# Schematic.net
KiCad netlist of a schematic drawn in EAGLE
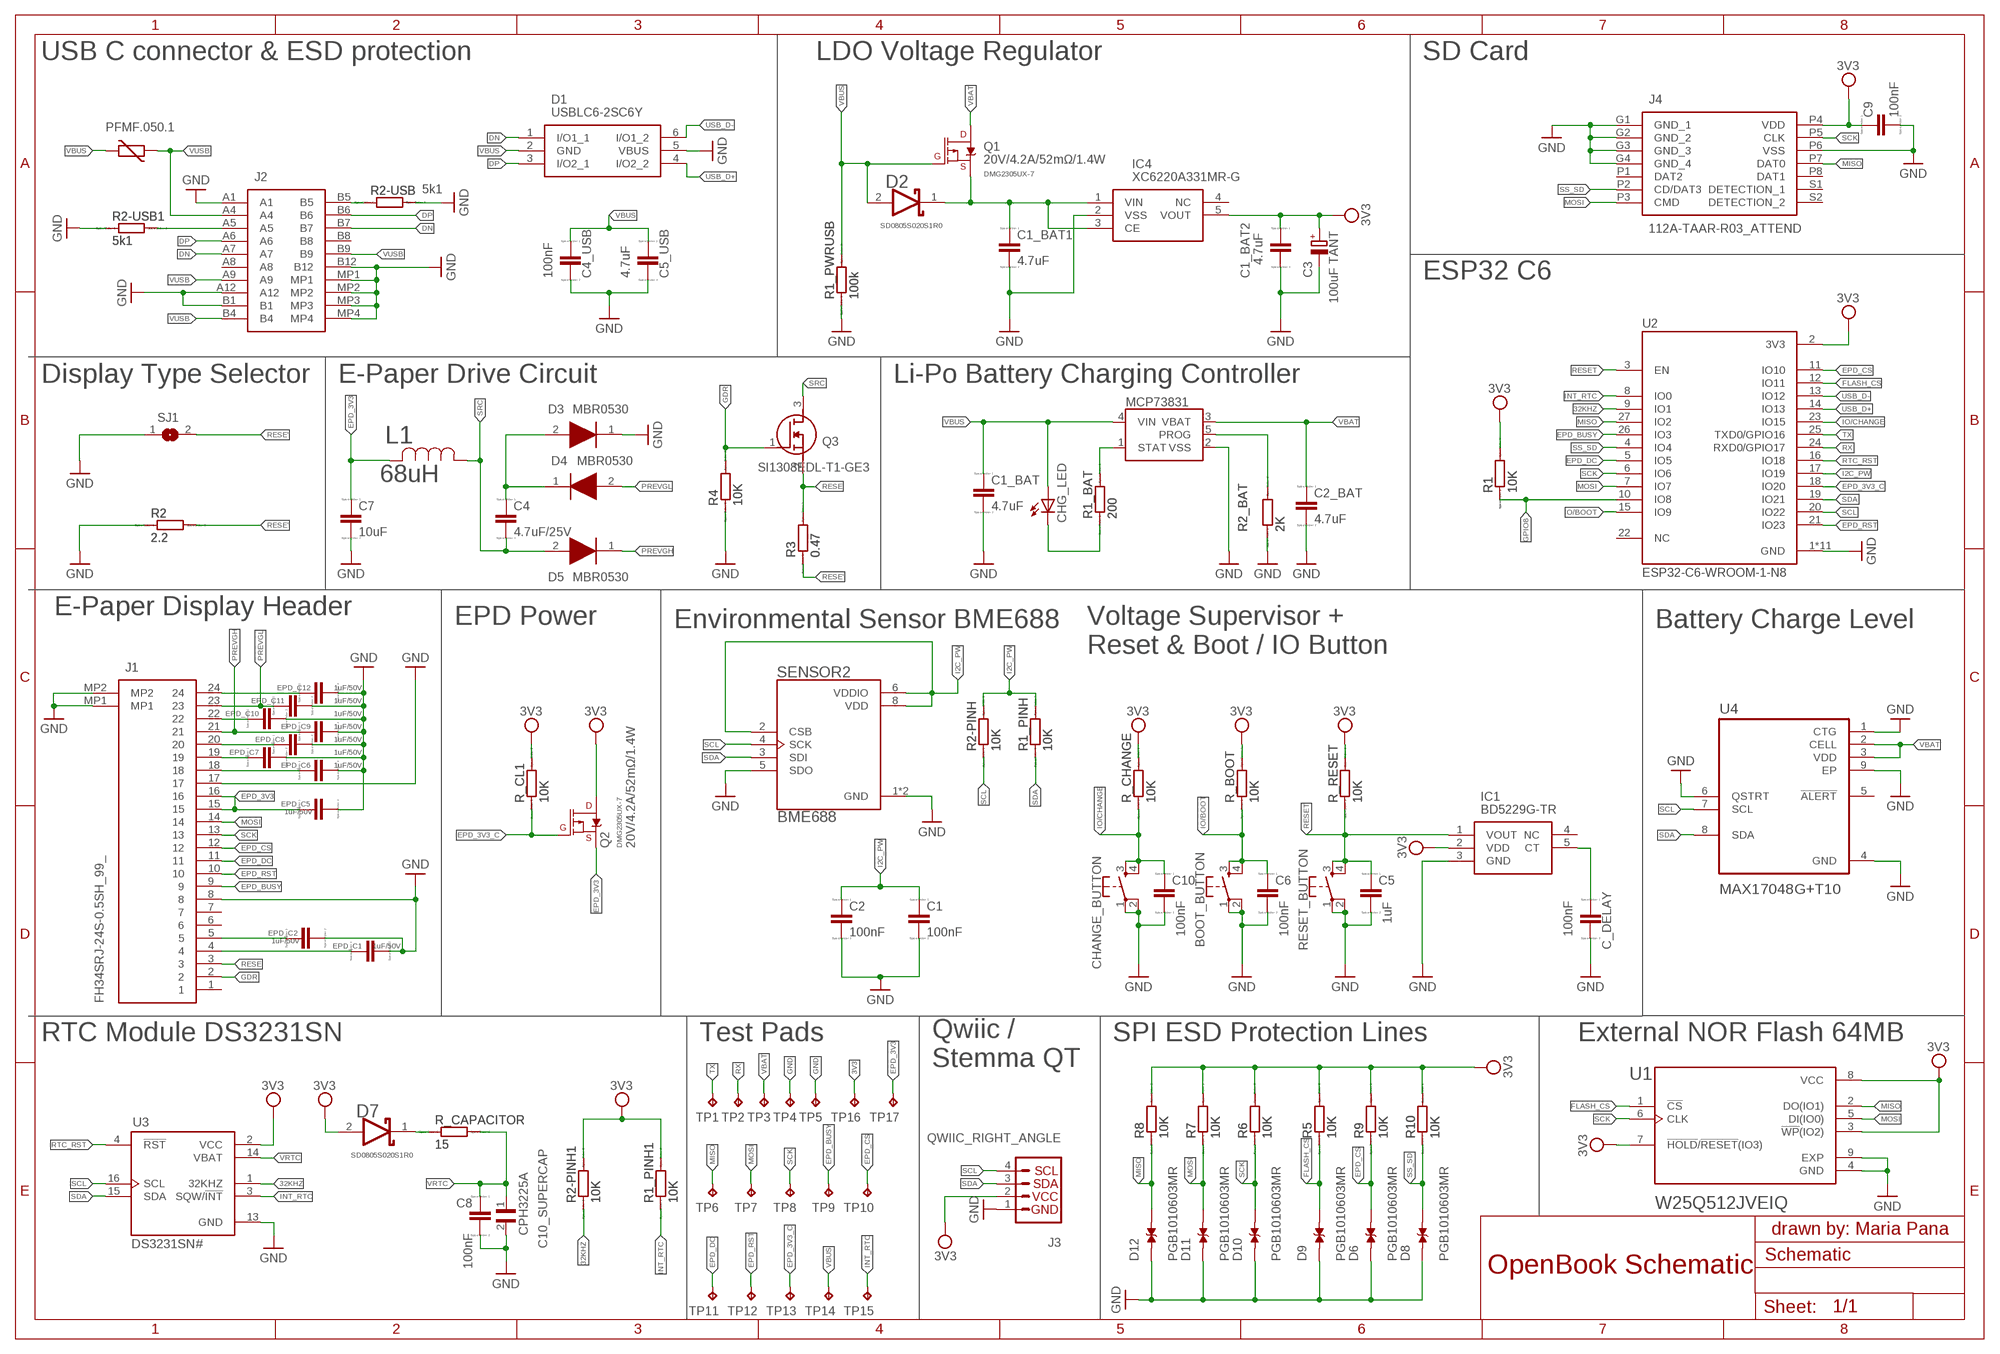
[diagram p0: schematic, sheet 1]

(export (version "E")
  (design (tool "Eeschema 10.0.6"))
  (components
    (comp (ref "BOOT_BUTTON")
      (value "BUTTON_CUSYOMV1")
      (footprint "eagle-import:MYBUTTON")
      (libsource (lib "eagle-import") (part "BUTTON_CUSYOMV1"))
    )
    (comp (ref "C1")
      (value "100nF")
      (footprint "eagle-import:ESP32_WROVER_EAGLE-LTSPICE_C0402")
      (libsource (lib "eagle-import") (part "ESP32_WROVER_EAGLE-LTSPICE_CC0402"))
    )
    (comp (ref "C1_BAT")
      (value "4.7uF")
      (footprint "eagle-import:EAGLE-LTSPICE_C0402")
      (libsource (lib "eagle-import") (part "EAGLE-LTSPICE_CC0402"))
    )
    (comp (ref "C1_BAT1")
      (value "4.7uF")
      (footprint "eagle-import:EAGLE-LTSPICE_C0402")
      (libsource (lib "eagle-import") (part "EAGLE-LTSPICE_CC0402"))
    )
    (comp (ref "C1_BAT2")
      (value "4.7uF")
      (footprint "eagle-import:EAGLE-LTSPICE_C0402")
      (libsource (lib "eagle-import") (part "EAGLE-LTSPICE_CC0402"))
    )
    (comp (ref "C2")
      (value "100nF")
      (footprint "eagle-import:ESP32_WROVER_EAGLE-LTSPICE_C0402")
      (libsource (lib "eagle-import") (part "ESP32_WROVER_EAGLE-LTSPICE_CC0402"))
    )
    (comp (ref "C2_BAT")
      (value "4.7uF")
      (footprint "eagle-import:EAGLE-LTSPICE_C0402")
      (libsource (lib "eagle-import") (part "EAGLE-LTSPICE_CC0402"))
    )
    (comp (ref "C3")
      (value "100uF TANT")
      (footprint "eagle-import:RCL_CT3528")
      (libsource (lib "eagle-import") (part "RCL_CPOL-EUCT3528"))
    )
    (comp (ref "C4")
      (value "4.7uF/25V")
      (footprint "eagle-import:EAGLE-LTSPICE_C0402")
      (libsource (lib "eagle-import") (part "EAGLE-LTSPICE_CC0402"))
    )
    (comp (ref "C4_USB")
      (value "100nF")
      (footprint "eagle-import:EAGLE-LTSPICE_C0402")
      (libsource (lib "eagle-import") (part "EAGLE-LTSPICE_CC0402"))
    )
    (comp (ref "C5")
      (value "1uF")
      (footprint "eagle-import:ESP32_WROVER_EAGLE-LTSPICE_C0402")
      (libsource (lib "eagle-import") (part "ESP32_WROVER_EAGLE-LTSPICE_CC0402"))
    )
    (comp (ref "C5_USB")
      (value "4.7uF")
      (footprint "eagle-import:EAGLE-LTSPICE_C0402")
      (libsource (lib "eagle-import") (part "EAGLE-LTSPICE_CC0402"))
    )
    (comp (ref "C6")
      (value "100nF")
      (footprint "eagle-import:ESP32_WROVER_EAGLE-LTSPICE_C0402")
      (libsource (lib "eagle-import") (part "ESP32_WROVER_EAGLE-LTSPICE_CC0402"))
    )
    (comp (ref "C7")
      (value "10uF")
      (footprint "eagle-import:EAGLE-LTSPICE_C0402")
      (libsource (lib "eagle-import") (part "EAGLE-LTSPICE_CC0402"))
    )
    (comp (ref "C8")
      (value "100nF")
      (footprint "eagle-import:ESP32_WROVER_EAGLE-LTSPICE_C0402")
      (libsource (lib "eagle-import") (part "ESP32_WROVER_EAGLE-LTSPICE_CC0402"))
    )
    (comp (ref "C9")
      (value "100nF")
      (footprint "eagle-import:EAGLE-LTSPICE_C0402")
      (libsource (lib "eagle-import") (part "EAGLE-LTSPICE_CC0402"))
    )
    (comp (ref "C10")
      (value "100nF")
      (footprint "eagle-import:ESP32_WROVER_EAGLE-LTSPICE_C0402")
      (libsource (lib "eagle-import") (part "ESP32_WROVER_EAGLE-LTSPICE_CC0402"))
    )
    (comp (ref "C10_SUPERCAP")
      (value "CPH3225A")
      (footprint "eagle-import:CAPCP3225X100N")
      (fields (field (name "MF") "Seiko Instruments"))
      (libsource (lib "eagle-import") (part "CPH3225A"))
    )
    (comp (ref "CHANGE_BUTTON")
      (value "BUTTON_CUSYOMV1")
      (footprint "eagle-import:MYBUTTON")
      (libsource (lib "eagle-import") (part "BUTTON_CUSYOMV1"))
    )
    (comp (ref "CHG_LED")
      (value "ADAFRUIT_LEDCHIP-LED0603")
      (footprint "eagle-import:ADAFRUIT_CHIP-LED0603")
      (libsource (lib "eagle-import") (part "ADAFRUIT_LEDCHIP-LED0603"))
    )
    (comp (ref "C_DELAY")
      (value "100nF")
      (footprint "eagle-import:ESP32_WROVER_EAGLE-LTSPICE_C0402")
      (libsource (lib "eagle-import") (part "ESP32_WROVER_EAGLE-LTSPICE_CC0402"))
    )
    (comp (ref "D1")
      (value "USBLC6-2SC6Y")
      (footprint "eagle-import:SOT95P280X145-6N")
      (fields (field (name "MF") "STMicroelectronics"))
      (libsource (lib "eagle-import") (part "USBLC6-2SC6Y"))
    )
    (comp (ref "D2")
      (value "SD0805S020S1R0")
      (footprint "eagle-import:ESP32_WROVER_AVX---SD0805S020S1R0_AVX_SD0805S020S1R0_0")
      (fields
        (field (name "DIGIKEY_PART_NUMBER") "478-7800-1-ND")
        (field (name "MF") "AVX")
        (field (name "MOUSER_PART_NUMBER") "581-SD0805S020S1R0")
      )
      (libsource (lib "eagle-import") (part "ESP32_WROVER_AVX---SD0805S020S1R0_AVX_SD0805S020S1R0_0_0AVX_SD0805S020S1R0_0_0"))
    )
    (comp (ref "D3")
      (value "MBR0530")
      (footprint "eagle-import:SOD3716X135N")
      (fields (field (name "MF") "ON Semiconductor"))
      (libsource (lib "eagle-import") (part "MBR0530"))
    )
    (comp (ref "D4")
      (value "MBR0530")
      (footprint "eagle-import:SOD3716X135N")
      (fields (field (name "MF") "ON Semiconductor"))
      (libsource (lib "eagle-import") (part "MBR0530"))
    )
    (comp (ref "D5")
      (value "MBR0530")
      (footprint "eagle-import:SOD3716X135N")
      (fields (field (name "MF") "ON Semiconductor"))
      (libsource (lib "eagle-import") (part "MBR0530"))
    )
    (comp (ref "D6")
      (value "PGB1010603MR")
      (footprint "eagle-import:DIOC1608X36N")
      (fields (field (name "MF") "Littelfuse Inc."))
      (libsource (lib "eagle-import") (part "PGB1010603MR"))
    )
    (comp (ref "D7")
      (value "ESP32_WROVER_AVX---SD0805S020S1R0_AVX_SD0805S020S1R0_0_0AVX_SD0805S020S1R0_0_0")
      (footprint "eagle-import:ESP32_WROVER_AVX---SD0805S020S1R0_AVX_SD0805S020S1R0_0")
      (fields
        (field (name "DIGIKEY_PART_NUMBER") "478-7800-1-ND")
        (field (name "MF") "AVX")
        (field (name "MOUSER_PART_NUMBER") "581-SD0805S020S1R0")
      )
      (libsource (lib "eagle-import") (part "ESP32_WROVER_AVX---SD0805S020S1R0_AVX_SD0805S020S1R0_0_0AVX_SD0805S020S1R0_0_0"))
    )
    (comp (ref "D8")
      (value "PGB1010603MR")
      (footprint "eagle-import:DIOC1608X36N")
      (fields (field (name "MF") "Littelfuse Inc."))
      (libsource (lib "eagle-import") (part "PGB1010603MR"))
    )
    (comp (ref "D9")
      (value "PGB1010603MR")
      (footprint "eagle-import:DIOC1608X36N")
      (fields (field (name "MF") "Littelfuse Inc."))
      (libsource (lib "eagle-import") (part "PGB1010603MR"))
    )
    (comp (ref "D10")
      (value "PGB1010603MR")
      (footprint "eagle-import:DIOC1608X36N")
      (fields (field (name "MF") "Littelfuse Inc."))
      (libsource (lib "eagle-import") (part "PGB1010603MR"))
    )
    (comp (ref "D11")
      (value "PGB1010603MR")
      (footprint "eagle-import:DIOC1608X36N")
      (fields (field (name "MF") "Littelfuse Inc."))
      (libsource (lib "eagle-import") (part "PGB1010603MR"))
    )
    (comp (ref "D12")
      (value "PGB1010603MR")
      (footprint "eagle-import:DIOC1608X36N")
      (fields (field (name "MF") "Littelfuse Inc."))
      (libsource (lib "eagle-import") (part "PGB1010603MR"))
    )
    (comp (ref "EPD_C1")
      (value "1uF/50V")
      (footprint "eagle-import:ESP32_WROVER_EAGLE-LTSPICE_C0402")
      (libsource (lib "eagle-import") (part "ESP32_WROVER_EAGLE-LTSPICE_CC0402"))
    )
    (comp (ref "EPD_C2")
      (value "1uF/50V")
      (footprint "eagle-import:ESP32_WROVER_EAGLE-LTSPICE_C0402")
      (libsource (lib "eagle-import") (part "ESP32_WROVER_EAGLE-LTSPICE_CC0402"))
    )
    (comp (ref "EPD_C5")
      (value "1uF/50V")
      (footprint "eagle-import:ESP32_WROVER_EAGLE-LTSPICE_C0402")
      (libsource (lib "eagle-import") (part "ESP32_WROVER_EAGLE-LTSPICE_CC0402"))
    )
    (comp (ref "EPD_C6")
      (value "1uF/50V")
      (footprint "eagle-import:ESP32_WROVER_EAGLE-LTSPICE_C0402")
      (libsource (lib "eagle-import") (part "ESP32_WROVER_EAGLE-LTSPICE_CC0402"))
    )
    (comp (ref "EPD_C7")
      (value "1uF/50V")
      (footprint "eagle-import:ESP32_WROVER_EAGLE-LTSPICE_C0402")
      (libsource (lib "eagle-import") (part "ESP32_WROVER_EAGLE-LTSPICE_CC0402"))
    )
    (comp (ref "EPD_C8")
      (value "1uF/50V")
      (footprint "eagle-import:ESP32_WROVER_EAGLE-LTSPICE_C0402")
      (libsource (lib "eagle-import") (part "ESP32_WROVER_EAGLE-LTSPICE_CC0402"))
    )
    (comp (ref "EPD_C9")
      (value "1uF/50V")
      (footprint "eagle-import:ESP32_WROVER_EAGLE-LTSPICE_C0402")
      (libsource (lib "eagle-import") (part "ESP32_WROVER_EAGLE-LTSPICE_CC0402"))
    )
    (comp (ref "EPD_C10")
      (value "1uF/50V")
      (footprint "eagle-import:ESP32_WROVER_EAGLE-LTSPICE_C0402")
      (libsource (lib "eagle-import") (part "ESP32_WROVER_EAGLE-LTSPICE_CC0402"))
    )
    (comp (ref "EPD_C11")
      (value "1uF/50V")
      (footprint "eagle-import:ESP32_WROVER_EAGLE-LTSPICE_C0402")
      (libsource (lib "eagle-import") (part "ESP32_WROVER_EAGLE-LTSPICE_CC0402"))
    )
    (comp (ref "EPD_C12")
      (value "1uF/50V")
      (footprint "eagle-import:ESP32_WROVER_EAGLE-LTSPICE_C0402")
      (libsource (lib "eagle-import") (part "ESP32_WROVER_EAGLE-LTSPICE_CC0402"))
    )
    (comp (ref "IC1")
      (value "BD5229G-TR")
      (footprint "eagle-import:SOT95P280X125-5N")
      (fields (field (name "MOUSER_PART_NUMBER") "755-BD5229G-TR"))
      (libsource (lib "eagle-import") (part "BD5229G-TR"))
    )
    (comp (ref "IC4")
      (value "XC6220A331MR-G")
      (footprint "eagle-import:SOT95P280X120-5N")
      (fields (field (name "MOUSER_PART_NUMBER") "865-XC6220A331MR-G"))
      (libsource (lib "eagle-import") (part "XC6220A331MR-G"))
    )
    (comp (ref "J1")
      (value "FH34SRJ-24S-0.5SH_99_")
      (footprint "eagle-import:FH34SRJ24S05SH99")
      (fields
        (field (name "MANUFACTURER_PART_NUMBER") "FH34SRJ-24S-0.5SH(99)")
        (field (name "MOUSER_PART_NUMBER") "798-FH34SRJ24S05SH99")
      )
      (libsource (lib "eagle-import") (part "FH34SRJ-24S-0.5SH_99_"))
    )
    (comp (ref "J2")
      (value "SAMACSYS_PARTS_USB4110-GF-A")
      (footprint "eagle-import:SAMACSYS_PARTS_USB4110GFA")
      (fields
        (field (name "MANUFACTURER_PART_NUMBER") "USB4110-GF-A")
        (field (name "MOUSER_PART_NUMBER") "640-USB4110-GF-A")
      )
      (libsource (lib "eagle-import") (part "SAMACSYS_PARTS_USB4110-GF-A"))
    )
    (comp (ref "J3")
      (value "QWIIC_RIGHT_ANGLE")
      (footprint "eagle-import:JST04_1MM_RA")
      (libsource (lib "eagle-import") (part "QWIIC_CONNECTORJS-1MM"))
    )
    (comp (ref "J4")
      (value "112A-TAAR-R03_ATTEND")
      (footprint "eagle-import:112ATAARR03ATTEND")
      (fields (field (name "MANUFACTURER_PART_NUMBER") "112A-TAAR-R03 ATTEND"))
      (libsource (lib "eagle-import") (part "112A-TAAR-R03_ATTEND"))
    )
    (comp (ref "L1")
      (value "68uH")
      (footprint "eagle-import:IND_4828-WE-TPC_WRE")
      (fields
        (field (name "MANUFACTURER_PART_NUMBER") "744043680")
        (field (name "COPYRIGHT") "Copyright (C) 2024 Ultra Librarian. All rights reserved.")
      )
      (libsource (lib "eagle-import") (part "744043680IND_4828-WE-TPC_WRE"))
    )
    (comp (ref "MCP73831")
      (value "ESP32_WROVER_SPARKFUN-IC-POWER_MCP73831")
      (footprint "eagle-import:ESP32_WROVER_SPARKFUN-IC-POWER_SOT23-5")
      (libsource (lib "eagle-import") (part "ESP32_WROVER_SPARKFUN-IC-POWER_MCP73831"))
    )
    (comp (ref "PFMF.050.1")
      (value "ESP32C6_VARISTORCN1812")
      (footprint "eagle-import:ESP32C6_VARISTOR_CT_CN1812")
      (libsource (lib "eagle-import") (part "ESP32C6_VARISTORCN1812"))
    )
    (comp (ref "Q1")
      (value "20V/4.2A/52mΩ/1.4W")
      (footprint "eagle-import:ESP32_WROVER_SPARKFUN-DISCRETESEMI_SOT23-3")
      (libsource (lib "eagle-import") (part "ESP32_WROVER_SPARKFUN-DISCRETESEMI_MOSFET_PCH-DMG2305UX-7"))
    )
    (comp (ref "Q2")
      (value "20V/4.2A/52mΩ/1.4W")
      (footprint "eagle-import:ESP32_WROVER_SPARKFUN-DISCRETESEMI_SOT23-3")
      (libsource (lib "eagle-import") (part "ESP32_WROVER_SPARKFUN-DISCRETESEMI_MOSFET_PCH-DMG2305UX-7"))
    )
    (comp (ref "Q3")
      (value "SI1308EDL-T1-GE3")
      (footprint "eagle-import:SOT65P210X110-3N")
      (fields (field (name "MF") "Vishay Siliconix"))
      (libsource (lib "eagle-import") (part "SI1308EDL-T1-GE3"))
    )
    (comp (ref "R1")
      (value "10K")
      (footprint "eagle-import:ESP32_WROVER_EAGLE-LTSPICE_R0402")
      (libsource (lib "eagle-import") (part "ESP32_WROVER_EAGLE-LTSPICE_RR0402"))
    )
    (comp (ref "R1_BAT")
      (value "200")
      (footprint "eagle-import:ESP32_WROVER_EAGLE-LTSPICE_R0402")
      (libsource (lib "eagle-import") (part "ESP32_WROVER_EAGLE-LTSPICE_RR0402"))
    )
    (comp (ref "R1_PINH")
      (value "10K")
      (footprint "eagle-import:ESP32_WROVER_EAGLE-LTSPICE_R0402")
      (libsource (lib "eagle-import") (part "ESP32_WROVER_EAGLE-LTSPICE_RR0402"))
    )
    (comp (ref "R1_PINH1")
      (value "10K")
      (footprint "eagle-import:ESP32_WROVER_EAGLE-LTSPICE_R0402")
      (libsource (lib "eagle-import") (part "ESP32_WROVER_EAGLE-LTSPICE_RR0402"))
    )
    (comp (ref "R1_PWRUSB")
      (value "100k")
      (footprint "eagle-import:ESP32_WROVER_EAGLE-LTSPICE_R0402")
      (libsource (lib "eagle-import") (part "ESP32_WROVER_EAGLE-LTSPICE_RR0402"))
    )
    (comp (ref "R2")
      (value "2.2")
      (footprint "eagle-import:ESP32_WROVER_EAGLE-LTSPICE_R0402")
      (libsource (lib "eagle-import") (part "ESP32_WROVER_EAGLE-LTSPICE_RR0402"))
    )
    (comp (ref "R2-PINH")
      (value "10K")
      (footprint "eagle-import:ESP32_WROVER_EAGLE-LTSPICE_R0402")
      (libsource (lib "eagle-import") (part "ESP32_WROVER_EAGLE-LTSPICE_RR0402"))
    )
    (comp (ref "R2-PINH1")
      (value "10K")
      (footprint "eagle-import:ESP32_WROVER_EAGLE-LTSPICE_R0402")
      (libsource (lib "eagle-import") (part "ESP32_WROVER_EAGLE-LTSPICE_RR0402"))
    )
    (comp (ref "R2-USB")
      (value "5k1")
      (footprint "eagle-import:ESP32_WROVER_EAGLE-LTSPICE_R0402")
      (libsource (lib "eagle-import") (part "ESP32_WROVER_EAGLE-LTSPICE_RR0402"))
    )
    (comp (ref "R2-USB1")
      (value "5k1")
      (footprint "eagle-import:ESP32_WROVER_EAGLE-LTSPICE_R0402")
      (libsource (lib "eagle-import") (part "ESP32_WROVER_EAGLE-LTSPICE_RR0402"))
    )
    (comp (ref "R2_BAT")
      (value "2K")
      (footprint "eagle-import:ESP32_WROVER_EAGLE-LTSPICE_R0402")
      (libsource (lib "eagle-import") (part "ESP32_WROVER_EAGLE-LTSPICE_RR0402"))
    )
    (comp (ref "R3")
      (value "0.47")
      (footprint "eagle-import:ESP32_WROVER_EAGLE-LTSPICE_R0402")
      (libsource (lib "eagle-import") (part "ESP32_WROVER_EAGLE-LTSPICE_RR0402"))
    )
    (comp (ref "R4")
      (value "10K")
      (footprint "eagle-import:ESP32_WROVER_EAGLE-LTSPICE_R0402")
      (libsource (lib "eagle-import") (part "ESP32_WROVER_EAGLE-LTSPICE_RR0402"))
    )
    (comp (ref "R5")
      (value "10K")
      (footprint "eagle-import:ESP32_WROVER_EAGLE-LTSPICE_R0402")
      (libsource (lib "eagle-import") (part "ESP32_WROVER_EAGLE-LTSPICE_RR0402"))
    )
    (comp (ref "R6")
      (value "10K")
      (footprint "eagle-import:ESP32_WROVER_EAGLE-LTSPICE_R0402")
      (libsource (lib "eagle-import") (part "ESP32_WROVER_EAGLE-LTSPICE_RR0402"))
    )
    (comp (ref "R7")
      (value "10K")
      (footprint "eagle-import:ESP32_WROVER_EAGLE-LTSPICE_R0402")
      (libsource (lib "eagle-import") (part "ESP32_WROVER_EAGLE-LTSPICE_RR0402"))
    )
    (comp (ref "R8")
      (value "10K")
      (footprint "eagle-import:ESP32_WROVER_EAGLE-LTSPICE_R0402")
      (libsource (lib "eagle-import") (part "ESP32_WROVER_EAGLE-LTSPICE_RR0402"))
    )
    (comp (ref "R9")
      (value "10K")
      (footprint "eagle-import:ESP32_WROVER_EAGLE-LTSPICE_R0402")
      (libsource (lib "eagle-import") (part "ESP32_WROVER_EAGLE-LTSPICE_RR0402"))
    )
    (comp (ref "R10")
      (value "10K")
      (footprint "eagle-import:ESP32_WROVER_EAGLE-LTSPICE_R0402")
      (libsource (lib "eagle-import") (part "ESP32_WROVER_EAGLE-LTSPICE_RR0402"))
    )
    (comp (ref "RESET_BUTTON")
      (value "BUTTON_CUSYOMV1")
      (footprint "eagle-import:MYBUTTON")
      (libsource (lib "eagle-import") (part "BUTTON_CUSYOMV1"))
    )
    (comp (ref "R_BOOT")
      (value "10K")
      (footprint "eagle-import:ESP32_WROVER_EAGLE-LTSPICE_R0402")
      (libsource (lib "eagle-import") (part "ESP32_WROVER_EAGLE-LTSPICE_RR0402"))
    )
    (comp (ref "R_CAPACITOR")
      (value "15")
      (footprint "eagle-import:ESP32_WROVER_EAGLE-LTSPICE_R0402")
      (libsource (lib "eagle-import") (part "ESP32_WROVER_EAGLE-LTSPICE_RR0402"))
    )
    (comp (ref "R_CHANGE")
      (value "10K")
      (footprint "eagle-import:ESP32_WROVER_EAGLE-LTSPICE_R0402")
      (libsource (lib "eagle-import") (part "ESP32_WROVER_EAGLE-LTSPICE_RR0402"))
    )
    (comp (ref "R_CL1")
      (value "10K")
      (footprint "eagle-import:ESP32_WROVER_EAGLE-LTSPICE_R0402")
      (libsource (lib "eagle-import") (part "ESP32_WROVER_EAGLE-LTSPICE_RR0402"))
    )
    (comp (ref "R_RESET")
      (value "10K")
      (footprint "eagle-import:ESP32_WROVER_EAGLE-LTSPICE_R0402")
      (libsource (lib "eagle-import") (part "ESP32_WROVER_EAGLE-LTSPICE_RR0402"))
    )
    (comp (ref "SENSOR2")
      (value "ESP32_WROVER_BME680_BME680")
      (footprint "eagle-import:ESP32_WROVER_BME680_PSON80P300X300X100-8N")
      (fields (field (name "MF") "Bosch Sensortec") (field (name "MP") "BME680"))
      (libsource (lib "eagle-import") (part "ESP32_WROVER_BME680_BME680"))
    )
    (comp (ref "SJ1") (value "SJ") (footprint "eagle-import:SJ") (libsource (lib "eagle-import") (part "SJ")))
    (comp (ref "TP1")
      (value "TPTP20R")
      (footprint "eagle-import:TP20R")
      (libsource (lib "eagle-import") (part "TPTP20R"))
    )
    (comp (ref "TP2")
      (value "TPTP20R")
      (footprint "eagle-import:TP20R")
      (libsource (lib "eagle-import") (part "TPTP20R"))
    )
    (comp (ref "TP3")
      (value "TPTP20R")
      (footprint "eagle-import:TP20R")
      (libsource (lib "eagle-import") (part "TPTP20R"))
    )
    (comp (ref "TP4")
      (value "TPTP20R")
      (footprint "eagle-import:TP20R")
      (libsource (lib "eagle-import") (part "TPTP20R"))
    )
    (comp (ref "TP5")
      (value "TPTP20R")
      (footprint "eagle-import:TP20R")
      (libsource (lib "eagle-import") (part "TPTP20R"))
    )
    (comp (ref "TP6")
      (value "TPTP20R")
      (footprint "eagle-import:TP20R")
      (libsource (lib "eagle-import") (part "TPTP20R"))
    )
    (comp (ref "TP7")
      (value "TPTP20R")
      (footprint "eagle-import:TP20R")
      (libsource (lib "eagle-import") (part "TPTP20R"))
    )
    (comp (ref "TP8")
      (value "TPTP20R")
      (footprint "eagle-import:TP20R")
      (libsource (lib "eagle-import") (part "TPTP20R"))
    )
    (comp (ref "TP9")
      (value "TPTP20R")
      (footprint "eagle-import:TP20R")
      (libsource (lib "eagle-import") (part "TPTP20R"))
    )
    (comp (ref "TP10")
      (value "TPTP20R")
      (footprint "eagle-import:TP20R")
      (libsource (lib "eagle-import") (part "TPTP20R"))
    )
    (comp (ref "TP11")
      (value "TPTP20R")
      (footprint "eagle-import:TP20R")
      (libsource (lib "eagle-import") (part "TPTP20R"))
    )
    (comp (ref "TP12")
      (value "TPTP20R")
      (footprint "eagle-import:TP20R")
      (libsource (lib "eagle-import") (part "TPTP20R"))
    )
    (comp (ref "TP13")
      (value "TPTP20R")
      (footprint "eagle-import:TP20R")
      (libsource (lib "eagle-import") (part "TPTP20R"))
    )
    (comp (ref "TP14")
      (value "TPTP20R")
      (footprint "eagle-import:TP20R")
      (libsource (lib "eagle-import") (part "TPTP20R"))
    )
    (comp (ref "TP15")
      (value "TPTP20R")
      (footprint "eagle-import:TP20R")
      (libsource (lib "eagle-import") (part "TPTP20R"))
    )
    (comp (ref "TP16")
      (value "TPTP20R")
      (footprint "eagle-import:TP20R")
      (libsource (lib "eagle-import") (part "TPTP20R"))
    )
    (comp (ref "TP17")
      (value "TPTP20R")
      (footprint "eagle-import:TP20R")
      (libsource (lib "eagle-import") (part "TPTP20R"))
    )
    (comp (ref "U1")
      (value "W25Q512JVEIQ")
      (footprint "eagle-import:SON127P600X800X80-9N")
      (fields (field (name "MF") "Winbond Electronics"))
      (libsource (lib "eagle-import") (part "W25Q512JVEIQ"))
    )
    (comp (ref "U2")
      (value "ESP32-C6-WROOM-1-N8")
      (footprint "eagle-import:XCVR_ESP32-C6-WROOM-1-N8")
      (fields (field (name "MF") "Espressif Systems"))
      (libsource (lib "eagle-import") (part "ESP32-C6-WROOM-1-N8"))
    )
    (comp (ref "U3")
      (value "DS3231SN#")
      (footprint "eagle-import:SOIC127P1032X265-16N")
      (fields (field (name "MF") "Analog Devices"))
      (libsource (lib "eagle-import") (part "DS3231SN#"))
    )
    (comp (ref "U4")
      (value "MAX17048G+T10")
      (footprint "eagle-import:SON50P200X200X80-9N")
      (fields (field (name "MF") "Analog Devices"))
      (libsource (lib "eagle-import") (part "MAX17048G+T10"))
    )
  )
  (nets
    (net (code "1") (name "3V3") (class "Default")
      (node (ref "C1_BAT2") (pin "1") (pinfunction "1_1") (pintype "passive"))
      (node (ref "C3") (pin "+") (pinfunction "+_+") (pintype "passive"))
      (node (ref "C9") (pin "1") (pinfunction "1_1") (pintype "passive"))
      (node (ref "D7") (pin "2") (pinfunction "ANODE_2") (pintype "bidirectional"))
      (node (ref "IC1") (pin "2") (pinfunction "VDD_2") (pintype "bidirectional"))
      (node (ref "IC4") (pin "5") (pinfunction "VOUT_5") (pintype "bidirectional"))
      (node (ref "J3") (pin "2") (pinfunction "2_2") (pintype "power_in"))
      (node (ref "J4") (pin "P4") (pinfunction "VDD_P4") (pintype "bidirectional"))
      (node (ref "Q2") (pin "3") (pinfunction "D_3") (pintype "bidirectional"))
      (node (ref "R1") (pin "2") (pinfunction "2_2") (pintype "passive"))
      (node (ref "R10") (pin "2") (pinfunction "2_2") (pintype "passive"))
      (node (ref "R1_PINH1") (pin "2") (pinfunction "2_2") (pintype "passive"))
      (node (ref "R2-PINH1") (pin "2") (pinfunction "2_2") (pintype "passive"))
      (node (ref "R5") (pin "2") (pinfunction "2_2") (pintype "passive"))
      (node (ref "R6") (pin "2") (pinfunction "2_2") (pintype "passive"))
      (node (ref "R7") (pin "2") (pinfunction "2_2") (pintype "passive"))
      (node (ref "R8") (pin "2") (pinfunction "2_2") (pintype "passive"))
      (node (ref "R9") (pin "2") (pinfunction "2_2") (pintype "passive"))
      (node (ref "R_BOOT") (pin "2") (pinfunction "2_2") (pintype "passive"))
      (node (ref "R_CHANGE") (pin "2") (pinfunction "2_2") (pintype "passive"))
      (node (ref "R_CL1") (pin "2") (pinfunction "2_2") (pintype "passive"))
      (node (ref "R_RESET") (pin "2") (pinfunction "2_2") (pintype "passive"))
      (node (ref "TP16") (pin "TP") (pinfunction "TP_TP") (pintype "input"))
      (node (ref "U1") (pin "3") (pinfunction "~{WP}(IO2)_3") (pintype "bidirectional"))
      (node (ref "U1") (pin "7") (pinfunction "~{HOLD}/~{RESET}(IO3)_7") (pintype "bidirectional"))
      (node (ref "U1") (pin "8") (pinfunction "VCC_8") (pintype "power_in"))
      (node (ref "U2") (pin "2") (pinfunction "3V3_2") (pintype "power_in"))
      (node (ref "U3") (pin "2") (pinfunction "VCC_2") (pintype "power_in"))
    )
    (net (code "2") (name "32KHZ") (class "Default")
      (node (ref "R2-PINH1") (pin "1") (pinfunction "1_1") (pintype "passive"))
      (node (ref "U2") (pin "9") (pinfunction "IO1_9") (pintype "bidirectional"))
      (node (ref "U3") (pin "1") (pinfunction "32KHZ_1") (pintype "output"))
    )
    (net (code "3") (name "DN") (class "Default")
      (node (ref "D1") (pin "1") (pinfunction "I/O1_1_1") (pintype "bidirectional"))
      (node (ref "J2") (pin "A7") (pinfunction "A7_A7") (pintype "bidirectional"))
      (node (ref "J2") (pin "B7") (pinfunction "B7_B7") (pintype "bidirectional"))
    )
    (net (code "4") (name "DP") (class "Default")
      (node (ref "D1") (pin "3") (pinfunction "I/O2_1_3") (pintype "bidirectional"))
      (node (ref "J2") (pin "A6") (pinfunction "A6_A6") (pintype "bidirectional"))
      (node (ref "J2") (pin "B6") (pinfunction "B6_B6") (pintype "bidirectional"))
    )
    (net (code "5") (name "EPD_3V3") (class "Default")
      (node (ref "C7") (pin "1") (pinfunction "1_1") (pintype "passive"))
      (node (ref "EPD_C5") (pin "1") (pinfunction "1_1") (pintype "passive"))
      (node (ref "J1") (pin "15") (pinfunction "15_15") (pintype "bidirectional"))
      (node (ref "J1") (pin "16") (pinfunction "16_16") (pintype "bidirectional"))
      (node (ref "L1") (pin "2") (pinfunction "2_2") (pintype "passive"))
      (node (ref "Q2") (pin "2") (pinfunction "S_2") (pintype "bidirectional"))
      (node (ref "TP17") (pin "TP") (pinfunction "TP_TP") (pintype "input"))
    )
    (net (code "6") (name "EPD_3V3_C") (class "Default")
      (node (ref "Q2") (pin "1") (pinfunction "G_1") (pintype "bidirectional"))
      (node (ref "R_CL1") (pin "1") (pinfunction "1_1") (pintype "passive"))
      (node (ref "TP13") (pin "TP") (pinfunction "TP_TP") (pintype "input"))
      (node (ref "U2") (pin "18") (pinfunction "IO20_18") (pintype "bidirectional"))
    )
    (net (code "7") (name "EPD_BUSY") (class "Default")
      (node (ref "J1") (pin "9") (pinfunction "9_9") (pintype "bidirectional"))
      (node (ref "TP9") (pin "TP") (pinfunction "TP_TP") (pintype "input"))
      (node (ref "U2") (pin "26") (pinfunction "IO3_26") (pintype "bidirectional"))
    )
    (net (code "8") (name "EPD_CS") (class "Default")
      (node (ref "D6") (pin "2") (pinfunction "2_2") (pintype "passive"))
      (node (ref "J1") (pin "12") (pinfunction "12_12") (pintype "bidirectional"))
      (node (ref "R9") (pin "1") (pinfunction "1_1") (pintype "passive"))
      (node (ref "TP10") (pin "TP") (pinfunction "TP_TP") (pintype "input"))
      (node (ref "U2") (pin "11") (pinfunction "IO10_11") (pintype "bidirectional"))
    )
    (net (code "9") (name "EPD_DC") (class "Default")
      (node (ref "J1") (pin "11") (pinfunction "11_11") (pintype "bidirectional"))
      (node (ref "TP11") (pin "TP") (pinfunction "TP_TP") (pintype "input"))
      (node (ref "U2") (pin "5") (pinfunction "IO5_5") (pintype "bidirectional"))
    )
    (net (code "10") (name "EPD_RST") (class "Default")
      (node (ref "J1") (pin "10") (pinfunction "10_10") (pintype "bidirectional"))
      (node (ref "TP12") (pin "TP") (pinfunction "TP_TP") (pintype "input"))
      (node (ref "U2") (pin "21") (pinfunction "IO23_21") (pintype "bidirectional"))
    )
    (net (code "11") (name "FLASH_CS") (class "Default")
      (node (ref "D9") (pin "2") (pinfunction "2_2") (pintype "passive"))
      (node (ref "R5") (pin "1") (pinfunction "1_1") (pintype "passive"))
      (node (ref "U1") (pin "1") (pinfunction "~{CS}_1") (pintype "input"))
      (node (ref "U2") (pin "12") (pinfunction "IO11_12") (pintype "bidirectional"))
    )
    (net (code "12") (name "GDR") (class "Default")
      (node (ref "J1") (pin "2") (pinfunction "2_2") (pintype "bidirectional"))
      (node (ref "Q3") (pin "1") (pinfunction "G_1") (pintype "bidirectional"))
      (node (ref "R4") (pin "2") (pinfunction "2_2") (pintype "passive"))
    )
    (net (code "13") (name "GND") (class "Default")
      (node (ref "BOOT_BUTTON") (pin "1") (pinfunction "1_1") (pintype "passive"))
      (node (ref "BOOT_BUTTON") (pin "2") (pinfunction "2_2") (pintype "passive"))
      (node (ref "C1") (pin "2") (pinfunction "2_2") (pintype "passive"))
      (node (ref "C10") (pin "2") (pinfunction "2_2") (pintype "passive"))
      (node (ref "C10_SUPERCAP") (pin "2") (pinfunction "2_2") (pintype "passive"))
      (node (ref "C1_BAT") (pin "2") (pinfunction "2_2") (pintype "passive"))
      (node (ref "C1_BAT1") (pin "2") (pinfunction "2_2") (pintype "passive"))
      (node (ref "C1_BAT2") (pin "2") (pinfunction "2_2") (pintype "passive"))
      (node (ref "C2") (pin "2") (pinfunction "2_2") (pintype "passive"))
      (node (ref "C2_BAT") (pin "2") (pinfunction "2_2") (pintype "passive"))
      (node (ref "C3") (pin "-") (pinfunction "-_-") (pintype "passive"))
      (node (ref "C4_USB") (pin "2") (pinfunction "2_2") (pintype "passive"))
      (node (ref "C5") (pin "2") (pinfunction "2_2") (pintype "passive"))
      (node (ref "C5_USB") (pin "2") (pinfunction "2_2") (pintype "passive"))
      (node (ref "C6") (pin "2") (pinfunction "2_2") (pintype "passive"))
      (node (ref "C7") (pin "2") (pinfunction "2_2") (pintype "passive"))
      (node (ref "C8") (pin "2") (pinfunction "2_2") (pintype "passive"))
      (node (ref "C9") (pin "2") (pinfunction "2_2") (pintype "passive"))
      (node (ref "CHANGE_BUTTON") (pin "1") (pinfunction "1_1") (pintype "passive"))
      (node (ref "CHANGE_BUTTON") (pin "2") (pinfunction "2_2") (pintype "passive"))
      (node (ref "C_DELAY") (pin "2") (pinfunction "2_2") (pintype "passive"))
      (node (ref "D1") (pin "5") (pinfunction "VBUS_5") (pintype "bidirectional"))
      (node (ref "D10") (pin "1") (pinfunction "1_1") (pintype "passive"))
      (node (ref "D11") (pin "1") (pinfunction "1_1") (pintype "passive"))
      (node (ref "D12") (pin "1") (pinfunction "1_1") (pintype "passive"))
      (node (ref "D3") (pin "1") (pinfunction "K_1") (pintype "bidirectional"))
      (node (ref "D6") (pin "1") (pinfunction "1_1") (pintype "passive"))
      (node (ref "D8") (pin "1") (pinfunction "1_1") (pintype "passive"))
      (node (ref "D9") (pin "1") (pinfunction "1_1") (pintype "passive"))
      (node (ref "EPD_C1") (pin "2") (pinfunction "2_2") (pintype "passive"))
      (node (ref "EPD_C10") (pin "2") (pinfunction "2_2") (pintype "passive"))
      (node (ref "EPD_C11") (pin "2") (pinfunction "2_2") (pintype "passive"))
      (node (ref "EPD_C12") (pin "2") (pinfunction "2_2") (pintype "passive"))
      (node (ref "EPD_C2") (pin "2") (pinfunction "2_2") (pintype "passive"))
      (node (ref "EPD_C5") (pin "2") (pinfunction "2_2") (pintype "passive"))
      (node (ref "EPD_C6") (pin "2") (pinfunction "2_2") (pintype "passive"))
      (node (ref "EPD_C7") (pin "2") (pinfunction "2_2") (pintype "passive"))
      (node (ref "EPD_C8") (pin "2") (pinfunction "2_2") (pintype "passive"))
      (node (ref "EPD_C9") (pin "2") (pinfunction "2_2") (pintype "passive"))
      (node (ref "IC1") (pin "3") (pinfunction "GND_3") (pintype "bidirectional"))
      (node (ref "IC4") (pin "2") (pinfunction "VSS_2") (pintype "bidirectional"))
      (node (ref "J1") (pin "17") (pinfunction "17_17") (pintype "bidirectional"))
      (node (ref "J1") (pin "8") (pinfunction "8_8") (pintype "bidirectional"))
      (node (ref "J1") (pin "MP1") (pinfunction "MP1_MP1") (pintype "bidirectional"))
      (node (ref "J1") (pin "MP2") (pinfunction "MP2_MP2") (pintype "bidirectional"))
      (node (ref "J2") (pin "A1") (pinfunction "A1_A1") (pintype "bidirectional"))
      (node (ref "J2") (pin "A12") (pinfunction "A12_A12") (pintype "bidirectional"))
      (node (ref "J2") (pin "B1") (pinfunction "B1_B1") (pintype "bidirectional"))
      (node (ref "J2") (pin "B12") (pinfunction "B12_B12") (pintype "bidirectional"))
      (node (ref "J2") (pin "MP1") (pinfunction "MP1_MP1") (pintype "bidirectional"))
      (node (ref "J2") (pin "MP2") (pinfunction "MP2_MP2") (pintype "bidirectional"))
      (node (ref "J2") (pin "MP3") (pinfunction "MP3_MP3") (pintype "bidirectional"))
      (node (ref "J2") (pin "MP4") (pinfunction "MP4_MP4") (pintype "bidirectional"))
      (node (ref "J3") (pin "1") (pinfunction "1_1") (pintype "power_in"))
      (node (ref "J4") (pin "G1") (pinfunction "GND_1_G1") (pintype "bidirectional"))
      (node (ref "J4") (pin "G2") (pinfunction "GND_2_G2") (pintype "bidirectional"))
      (node (ref "J4") (pin "G3") (pinfunction "GND_3_G3") (pintype "bidirectional"))
      (node (ref "J4") (pin "G4") (pinfunction "GND_4_G4") (pintype "bidirectional"))
      (node (ref "J4") (pin "P6") (pinfunction "VSS_P6") (pintype "bidirectional"))
      (node (ref "MCP73831") (pin "2") (pinfunction "VSS_2") (pintype "power_in"))
      (node (ref "R1_PWRUSB") (pin "1") (pinfunction "1_1") (pintype "passive"))
      (node (ref "R2") (pin "1") (pinfunction "1_1") (pintype "passive"))
      (node (ref "R2-USB") (pin "2") (pinfunction "2_2") (pintype "passive"))
      (node (ref "R2-USB1") (pin "1") (pinfunction "1_1") (pintype "passive"))
      (node (ref "R2_BAT") (pin "1") (pinfunction "1_1") (pintype "passive"))
      (node (ref "R4") (pin "1") (pinfunction "1_1") (pintype "passive"))
      (node (ref "RESET_BUTTON") (pin "1") (pinfunction "1_1") (pintype "passive"))
      (node (ref "RESET_BUTTON") (pin "2") (pinfunction "2_2") (pintype "passive"))
      (node (ref "SENSOR2") (pin "1") (pinfunction "GND_1") (pintype "power_in"))
      (node (ref "SENSOR2") (pin "5") (pinfunction "SDO_5") (pintype "bidirectional"))
      (node (ref "SENSOR2") (pin "7") (pinfunction "GND_7") (pintype "power_in"))
      (node (ref "SJ1") (pin "1") (pinfunction "1_1") (pintype "passive"))
      (node (ref "TP4") (pin "TP") (pinfunction "TP_TP") (pintype "input"))
      (node (ref "TP5") (pin "TP") (pinfunction "TP_TP") (pintype "input"))
      (node (ref "U1") (pin "4") (pinfunction "GND_4") (pintype "power_in"))
      (node (ref "U1") (pin "9") (pinfunction "EXP_9") (pintype "passive"))
      (node (ref "U2") (pin "1") (pinfunction "GND_1") (pintype "power_in"))
      (node (ref "U2") (pin "28") (pinfunction "GND_28") (pintype "power_in"))
      (node (ref "U2") (pin "29_1") (pinfunction "GND_29_1") (pintype "power_in"))
      (node (ref "U2") (pin "29_2") (pinfunction "GND_29_2") (pintype "power_in"))
      (node (ref "U2") (pin "29_3") (pinfunction "GND_29_3") (pintype "power_in"))
      (node (ref "U2") (pin "29_4") (pinfunction "GND_29_4") (pintype "power_in"))
      (node (ref "U2") (pin "29_5") (pinfunction "GND_29_5") (pintype "power_in"))
      (node (ref "U2") (pin "29_6") (pinfunction "GND_29_6") (pintype "power_in"))
      (node (ref "U2") (pin "29_7") (pinfunction "GND_29_7") (pintype "power_in"))
      (node (ref "U2") (pin "29_8") (pinfunction "GND_29_8") (pintype "power_in"))
      (node (ref "U2") (pin "29_9") (pinfunction "GND_29_9") (pintype "power_in"))
      (node (ref "U3") (pin "13") (pinfunction "GND_13") (pintype "power_in"))
      (node (ref "U4") (pin "1") (pinfunction "CTG_1") (pintype "power_in"))
      (node (ref "U4") (pin "4") (pinfunction "GND_4") (pintype "power_in"))
      (node (ref "U4") (pin "6") (pinfunction "QSTRT_6") (pintype "input"))
      (node (ref "U4") (pin "9") (pinfunction "EP_9") (pintype "power_in"))
    )
    (net (code "14") (name "GPIO8") (class "Default")
      (node (ref "R1") (pin "1") (pinfunction "1_1") (pintype "passive"))
      (node (ref "U2") (pin "10") (pinfunction "IO8_10") (pintype "bidirectional"))
    )
    (net (code "15") (name "I2C_PW") (class "Default")
      (node (ref "C1") (pin "1") (pinfunction "1_1") (pintype "passive"))
      (node (ref "C2") (pin "1") (pinfunction "1_1") (pintype "passive"))
      (node (ref "R1_PINH") (pin "2") (pinfunction "2_2") (pintype "passive"))
      (node (ref "R2-PINH") (pin "2") (pinfunction "2_2") (pintype "passive"))
      (node (ref "SENSOR2") (pin "2") (pinfunction "CSB_2") (pintype "input"))
      (node (ref "SENSOR2") (pin "6") (pinfunction "VDDIO_6") (pintype "power_in"))
      (node (ref "SENSOR2") (pin "8") (pinfunction "VDD_8") (pintype "power_in"))
      (node (ref "U2") (pin "17") (pinfunction "IO19_17") (pintype "bidirectional"))
    )
    (net (code "16") (name "INT_RTC") (class "Default")
      (node (ref "R1_PINH1") (pin "1") (pinfunction "1_1") (pintype "passive"))
      (node (ref "TP15") (pin "TP") (pinfunction "TP_TP") (pintype "input"))
      (node (ref "U2") (pin "8") (pinfunction "IO0_8") (pintype "bidirectional"))
      (node (ref "U3") (pin "3") (pinfunction "SQW/~{INT}_3") (pintype "output"))
    )
    (net (code "17") (name "IO{slash}BOOT") (class "Default")
      (node (ref "BOOT_BUTTON") (pin "3") (pinfunction "3_3") (pintype "passive"))
      (node (ref "BOOT_BUTTON") (pin "4") (pinfunction "4_4") (pintype "passive"))
      (node (ref "C6") (pin "1") (pinfunction "1_1") (pintype "passive"))
      (node (ref "R_BOOT") (pin "1") (pinfunction "1_1") (pintype "passive"))
      (node (ref "U2") (pin "15") (pinfunction "IO9_15") (pintype "bidirectional"))
    )
    (net (code "18") (name "IO{slash}CHANGE") (class "Default")
      (node (ref "C10") (pin "1") (pinfunction "1_1") (pintype "passive"))
      (node (ref "CHANGE_BUTTON") (pin "3") (pinfunction "3_3") (pintype "passive"))
      (node (ref "CHANGE_BUTTON") (pin "4") (pinfunction "4_4") (pintype "passive"))
      (node (ref "R_CHANGE") (pin "1") (pinfunction "1_1") (pintype "passive"))
      (node (ref "U2") (pin "23") (pinfunction "IO15_23") (pintype "bidirectional"))
    )
    (net (code "19") (name "MISO") (class "Default")
      (node (ref "D12") (pin "2") (pinfunction "2_2") (pintype "passive"))
      (node (ref "J4") (pin "P7") (pinfunction "DAT0_P7") (pintype "bidirectional"))
      (node (ref "R8") (pin "1") (pinfunction "1_1") (pintype "passive"))
      (node (ref "TP6") (pin "TP") (pinfunction "TP_TP") (pintype "input"))
      (node (ref "U1") (pin "2") (pinfunction "DO(IO1)_2") (pintype "bidirectional"))
      (node (ref "U2") (pin "27") (pinfunction "IO2_27") (pintype "bidirectional"))
    )
    (net (code "20") (name "MOSI") (class "Default")
      (node (ref "D11") (pin "2") (pinfunction "2_2") (pintype "passive"))
      (node (ref "J1") (pin "14") (pinfunction "14_14") (pintype "bidirectional"))
      (node (ref "J4") (pin "P3") (pinfunction "CMD_P3") (pintype "bidirectional"))
      (node (ref "R7") (pin "1") (pinfunction "1_1") (pintype "passive"))
      (node (ref "TP7") (pin "TP") (pinfunction "TP_TP") (pintype "input"))
      (node (ref "U1") (pin "5") (pinfunction "DI(IO0)_5") (pintype "bidirectional"))
      (node (ref "U2") (pin "7") (pinfunction "IO7_7") (pintype "bidirectional"))
    )
    (net (code "21") (name "Net-(CHG_LED-PadC)") (class "Default")
      (node (ref "CHG_LED") (pin "C") (pinfunction "C_C") (pintype "passive"))
      (node (ref "R1_BAT") (pin "1") (pinfunction "1_1") (pintype "passive"))
    )
    (net (code "22") (name "Net-(D2-CATHODE)") (class "Default")
      (node (ref "C1_BAT1") (pin "1") (pinfunction "1_1") (pintype "passive"))
      (node (ref "D2") (pin "1") (pinfunction "CATHODE_1") (pintype "bidirectional"))
      (node (ref "IC4") (pin "1") (pinfunction "VIN_1") (pintype "bidirectional"))
      (node (ref "IC4") (pin "3") (pinfunction "CE_3") (pintype "bidirectional"))
      (node (ref "Q1") (pin "2") (pinfunction "S_2") (pintype "bidirectional"))
    )
    (net (code "23") (name "Net-(D3-A)") (class "Default")
      (node (ref "C4") (pin "1") (pinfunction "1_1") (pintype "passive"))
      (node (ref "D3") (pin "2") (pinfunction "A_2") (pintype "bidirectional"))
      (node (ref "D4") (pin "1") (pinfunction "K_1") (pintype "bidirectional"))
    )
    (net (code "24") (name "Net-(D7-CATHODE)") (class "Default")
      (node (ref "D7") (pin "1") (pinfunction "CATHODE_1") (pintype "bidirectional"))
      (node (ref "R_CAPACITOR") (pin "1") (pinfunction "1_1") (pintype "passive"))
    )
    (net (code "25") (name "Net-(EPD_C1-Pad1)") (class "Default")
      (node (ref "EPD_C1") (pin "1") (pinfunction "1_1") (pintype "passive"))
      (node (ref "J1") (pin "4") (pinfunction "4_4") (pintype "bidirectional"))
    )
    (net (code "26") (name "Net-(EPD_C2-Pad1)") (class "Default")
      (node (ref "EPD_C2") (pin "1") (pinfunction "1_1") (pintype "passive"))
      (node (ref "J1") (pin "5") (pinfunction "5_5") (pintype "bidirectional"))
    )
    (net (code "27") (name "Net-(EPD_C6-Pad1)") (class "Default")
      (node (ref "EPD_C6") (pin "1") (pinfunction "1_1") (pintype "passive"))
      (node (ref "J1") (pin "18") (pinfunction "18_18") (pintype "bidirectional"))
    )
    (net (code "28") (name "Net-(EPD_C7-Pad1)") (class "Default")
      (node (ref "EPD_C7") (pin "1") (pinfunction "1_1") (pintype "passive"))
      (node (ref "J1") (pin "19") (pinfunction "19_19") (pintype "bidirectional"))
    )
    (net (code "29") (name "Net-(EPD_C8-Pad1)") (class "Default")
      (node (ref "EPD_C8") (pin "1") (pinfunction "1_1") (pintype "passive"))
      (node (ref "J1") (pin "20") (pinfunction "20_20") (pintype "bidirectional"))
    )
    (net (code "30") (name "Net-(EPD_C10-Pad1)") (class "Default")
      (node (ref "EPD_C10") (pin "1") (pinfunction "1_1") (pintype "passive"))
      (node (ref "J1") (pin "22") (pinfunction "22_22") (pintype "bidirectional"))
    )
    (net (code "31") (name "Net-(EPD_C12-Pad1)") (class "Default")
      (node (ref "EPD_C12") (pin "1") (pinfunction "1_1") (pintype "passive"))
      (node (ref "J1") (pin "24") (pinfunction "24_24") (pintype "bidirectional"))
    )
    (net (code "32") (name "Net-(IC1-CT)") (class "Default")
      (node (ref "C_DELAY") (pin "1") (pinfunction "1_1") (pintype "passive"))
      (node (ref "IC1") (pin "5") (pinfunction "CT_5") (pintype "bidirectional"))
    )
    (net (code "33") (name "Net-(J2-PadA5)") (class "Default")
      (node (ref "J2") (pin "A5") (pinfunction "A5_A5") (pintype "bidirectional"))
      (node (ref "R2-USB1") (pin "2") (pinfunction "2_2") (pintype "passive"))
    )
    (net (code "34") (name "Net-(J2-PadB5)") (class "Default")
      (node (ref "J2") (pin "B5") (pinfunction "B5_B5") (pintype "bidirectional"))
      (node (ref "R2-USB") (pin "1") (pinfunction "1_1") (pintype "passive"))
    )
    (net (code "35") (name "Net-(MCP73831-PROG)") (class "Default")
      (node (ref "MCP73831") (pin "5") (pinfunction "PROG_5") (pintype "input"))
      (node (ref "R2_BAT") (pin "2") (pinfunction "2_2") (pintype "passive"))
    )
    (net (code "36") (name "Net-(MCP73831-STAT)") (class "Default")
      (node (ref "MCP73831") (pin "1") (pinfunction "STAT_1") (pintype "output"))
      (node (ref "R1_BAT") (pin "2") (pinfunction "2_2") (pintype "passive"))
    )
    (net (code "37") (name "PREVGH") (class "Default")
      (node (ref "D5") (pin "1") (pinfunction "K_1") (pintype "bidirectional"))
      (node (ref "EPD_C9") (pin "1") (pinfunction "1_1") (pintype "passive"))
      (node (ref "J1") (pin "21") (pinfunction "21_21") (pintype "bidirectional"))
    )
    (net (code "38") (name "PREVGL") (class "Default")
      (node (ref "D4") (pin "2") (pinfunction "A_2") (pintype "bidirectional"))
      (node (ref "EPD_C11") (pin "1") (pinfunction "1_1") (pintype "passive"))
      (node (ref "J1") (pin "23") (pinfunction "23_23") (pintype "bidirectional"))
    )
    (net (code "39") (name "RESE") (class "Default")
      (node (ref "J1") (pin "3") (pinfunction "3_3") (pintype "bidirectional"))
      (node (ref "Q3") (pin "2") (pinfunction "S_2") (pintype "bidirectional"))
      (node (ref "R3") (pin "2") (pinfunction "2_2") (pintype "passive"))
    )
    (net (code "40") (name "RESE'") (class "Default")
      (node (ref "R2") (pin "2") (pinfunction "2_2") (pintype "passive"))
      (node (ref "R3") (pin "1") (pinfunction "1_1") (pintype "passive"))
      (node (ref "SJ1") (pin "2") (pinfunction "2_2") (pintype "passive"))
    )
    (net (code "41") (name "RESET") (class "Default")
      (node (ref "C5") (pin "1") (pinfunction "1_1") (pintype "passive"))
      (node (ref "IC1") (pin "1") (pinfunction "VOUT_1") (pintype "bidirectional"))
      (node (ref "RESET_BUTTON") (pin "3") (pinfunction "3_3") (pintype "passive"))
      (node (ref "RESET_BUTTON") (pin "4") (pinfunction "4_4") (pintype "passive"))
      (node (ref "R_RESET") (pin "1") (pinfunction "1_1") (pintype "passive"))
      (node (ref "U2") (pin "3") (pinfunction "EN_3") (pintype "input"))
    )
    (net (code "42") (name "RTC_RST") (class "Default")
      (node (ref "U2") (pin "16") (pinfunction "IO18_16") (pintype "bidirectional"))
      (node (ref "U3") (pin "4") (pinfunction "~{RST}_4") (pintype "input"))
    )
    (net (code "43") (name "RX") (class "Default")
      (node (ref "TP2") (pin "TP") (pinfunction "TP_TP") (pintype "input"))
      (node (ref "U2") (pin "24") (pinfunction "RXD0/GPIO17_24") (pintype "bidirectional"))
    )
    (net (code "44") (name "SCK") (class "Default")
      (node (ref "D10") (pin "2") (pinfunction "2_2") (pintype "passive"))
      (node (ref "J1") (pin "13") (pinfunction "13_13") (pintype "bidirectional"))
      (node (ref "J4") (pin "P5") (pinfunction "CLK_P5") (pintype "bidirectional"))
      (node (ref "R6") (pin "1") (pinfunction "1_1") (pintype "passive"))
      (node (ref "TP8") (pin "TP") (pinfunction "TP_TP") (pintype "input"))
      (node (ref "U1") (pin "6") (pinfunction "CLK_6") (pintype "input"))
      (node (ref "U2") (pin "6") (pinfunction "IO6_6") (pintype "bidirectional"))
    )
    (net (code "45") (name "SCL") (class "Default")
      (node (ref "J3") (pin "4") (pinfunction "4_4") (pintype "passive"))
      (node (ref "R2-PINH") (pin "1") (pinfunction "1_1") (pintype "passive"))
      (node (ref "SENSOR2") (pin "4") (pinfunction "SCK_4") (pintype "input"))
      (node (ref "U2") (pin "20") (pinfunction "IO22_20") (pintype "bidirectional"))
      (node (ref "U3") (pin "16") (pinfunction "SCL_16") (pintype "input"))
      (node (ref "U4") (pin "7") (pinfunction "SCL_7") (pintype "input"))
    )
    (net (code "46") (name "SDA") (class "Default")
      (node (ref "J3") (pin "3") (pinfunction "3_3") (pintype "passive"))
      (node (ref "R1_PINH") (pin "1") (pinfunction "1_1") (pintype "passive"))
      (node (ref "SENSOR2") (pin "3") (pinfunction "SDI_3") (pintype "bidirectional"))
      (node (ref "U2") (pin "19") (pinfunction "IO21_19") (pintype "bidirectional"))
      (node (ref "U3") (pin "15") (pinfunction "SDA_15") (pintype "bidirectional"))
      (node (ref "U4") (pin "8") (pinfunction "SDA_8") (pintype "bidirectional"))
    )
    (net (code "47") (name "SRC") (class "Default")
      (node (ref "C4") (pin "2") (pinfunction "2_2") (pintype "passive"))
      (node (ref "D5") (pin "2") (pinfunction "A_2") (pintype "bidirectional"))
      (node (ref "L1") (pin "1") (pinfunction "1_1") (pintype "passive"))
      (node (ref "Q3") (pin "3") (pinfunction "D_3") (pintype "bidirectional"))
    )
    (net (code "48") (name "SS_SD") (class "Default")
      (node (ref "D8") (pin "2") (pinfunction "2_2") (pintype "passive"))
      (node (ref "J4") (pin "P2") (pinfunction "CD/DAT3_P2") (pintype "bidirectional"))
      (node (ref "R10") (pin "1") (pinfunction "1_1") (pintype "passive"))
      (node (ref "U2") (pin "4") (pinfunction "IO4_4") (pintype "bidirectional"))
    )
    (net (code "49") (name "TX") (class "Default")
      (node (ref "TP1") (pin "TP") (pinfunction "TP_TP") (pintype "input"))
      (node (ref "U2") (pin "25") (pinfunction "TXD0/GPIO16_25") (pintype "bidirectional"))
    )
    (net (code "50") (name "USB_D+") (class "Default")
      (node (ref "D1") (pin "4") (pinfunction "I/O2_2_4") (pintype "bidirectional"))
      (node (ref "U2") (pin "14") (pinfunction "IO13_14") (pintype "bidirectional"))
    )
    (net (code "51") (name "USB_D-") (class "Default")
      (node (ref "D1") (pin "6") (pinfunction "I/O1_2_6") (pintype "bidirectional"))
      (node (ref "U2") (pin "13") (pinfunction "IO12_13") (pintype "bidirectional"))
    )
    (net (code "52") (name "VBAT") (class "Default")
      (node (ref "C2_BAT") (pin "1") (pinfunction "1_1") (pintype "passive"))
      (node (ref "MCP73831") (pin "3") (pinfunction "VBAT_3") (pintype "power_in"))
      (node (ref "Q1") (pin "3") (pinfunction "D_3") (pintype "bidirectional"))
      (node (ref "TP3") (pin "TP") (pinfunction "TP_TP") (pintype "input"))
      (node (ref "U4") (pin "2") (pinfunction "CELL_2") (pintype "power_in"))
      (node (ref "U4") (pin "3") (pinfunction "VDD_3") (pintype "power_in"))
    )
    (net (code "53") (name "VBUS") (class "Default")
      (node (ref "C1_BAT") (pin "1") (pinfunction "1_1") (pintype "passive"))
      (node (ref "C4_USB") (pin "1") (pinfunction "1_1") (pintype "passive"))
      (node (ref "C5_USB") (pin "1") (pinfunction "1_1") (pintype "passive"))
      (node (ref "CHG_LED") (pin "A") (pinfunction "A_A") (pintype "passive"))
      (node (ref "D1") (pin "2") (pinfunction "GND_2") (pintype "bidirectional"))
      (node (ref "D2") (pin "2") (pinfunction "ANODE_2") (pintype "bidirectional"))
      (node (ref "MCP73831") (pin "4") (pinfunction "VIN_4") (pintype "power_in"))
      (node (ref "PFMF.050.1") (pin "2") (pinfunction "2_2") (pintype "passive"))
      (node (ref "Q1") (pin "1") (pinfunction "G_1") (pintype "bidirectional"))
      (node (ref "R1_PWRUSB") (pin "2") (pinfunction "2_2") (pintype "passive"))
      (node (ref "TP14") (pin "TP") (pinfunction "TP_TP") (pintype "input"))
    )
    (net (code "54") (name "VRTC") (class "Default")
      (node (ref "C10_SUPERCAP") (pin "1") (pinfunction "1_1") (pintype "passive"))
      (node (ref "C8") (pin "1") (pinfunction "1_1") (pintype "passive"))
      (node (ref "R_CAPACITOR") (pin "2") (pinfunction "2_2") (pintype "passive"))
      (node (ref "U3") (pin "14") (pinfunction "VBAT_14") (pintype "power_in"))
    )
    (net (code "55") (name "VUSB") (class "Default")
      (node (ref "J2") (pin "A4") (pinfunction "A4_A4") (pintype "bidirectional"))
      (node (ref "J2") (pin "A9") (pinfunction "A9_A9") (pintype "bidirectional"))
      (node (ref "J2") (pin "B4") (pinfunction "B4_B4") (pintype "bidirectional"))
      (node (ref "J2") (pin "B9") (pinfunction "B9_B9") (pintype "bidirectional"))
      (node (ref "PFMF.050.1") (pin "1") (pinfunction "1_1") (pintype "passive"))
    )
    (net (code "56") (name "unconnected-(IC1-NC-Pad4)") (class "Default")
      (node (ref "IC1") (pin "4") (pinfunction "NC_4") (pintype "no_connect"))
    )
    (net (code "57") (name "unconnected-(IC4-NC-Pad4)") (class "Default")
      (node (ref "IC4") (pin "4") (pinfunction "NC_4") (pintype "no_connect"))
    )
    (net (code "58") (name "unconnected-(J1-Pad1)") (class "Default")
      (node (ref "J1") (pin "1") (pinfunction "1_1") (pintype "bidirectional"))
    )
    (net (code "59") (name "unconnected-(J1-Pad6)") (class "Default")
      (node (ref "J1") (pin "6") (pinfunction "6_6") (pintype "bidirectional"))
    )
    (net (code "60") (name "unconnected-(J1-Pad7)") (class "Default")
      (node (ref "J1") (pin "7") (pinfunction "7_7") (pintype "bidirectional"))
    )
    (net (code "61") (name "unconnected-(J2-PadA8)") (class "Default")
      (node (ref "J2") (pin "A8") (pinfunction "A8_A8") (pintype "bidirectional"))
    )
    (net (code "62") (name "unconnected-(J2-PadB8)") (class "Default")
      (node (ref "J2") (pin "B8") (pinfunction "B8_B8") (pintype "bidirectional"))
    )
    (net (code "63") (name "unconnected-(J4-DAT1-PadP8)") (class "Default")
      (node (ref "J4") (pin "P8") (pinfunction "DAT1_P8") (pintype "bidirectional"))
    )
    (net (code "64") (name "unconnected-(J4-DAT2-PadP1)") (class "Default")
      (node (ref "J4") (pin "P1") (pinfunction "DAT2_P1") (pintype "bidirectional"))
    )
    (net (code "65") (name "unconnected-(J4-DETECTION_1-PadS1)") (class "Default")
      (node (ref "J4") (pin "S1") (pinfunction "DETECTION_1_S1") (pintype "bidirectional"))
    )
    (net (code "66") (name "unconnected-(J4-DETECTION_2-PadS2)") (class "Default")
      (node (ref "J4") (pin "S2") (pinfunction "DETECTION_2_S2") (pintype "bidirectional"))
    )
    (net (code "67") (name "unconnected-(U2-NC-Pad22)") (class "Default")
      (node (ref "U2") (pin "22") (pinfunction "NC_22") (pintype "no_connect"))
    )
    (net (code "68") (name "unconnected-(U4-~{ALERT}-Pad5)") (class "Default")
      (node (ref "U4") (pin "5") (pinfunction "~{ALERT}_5") (pintype "output"))
    )
  )
)
